# MP257_18x18.net
KiCad netlist of a schematic drawn in Altium Designer
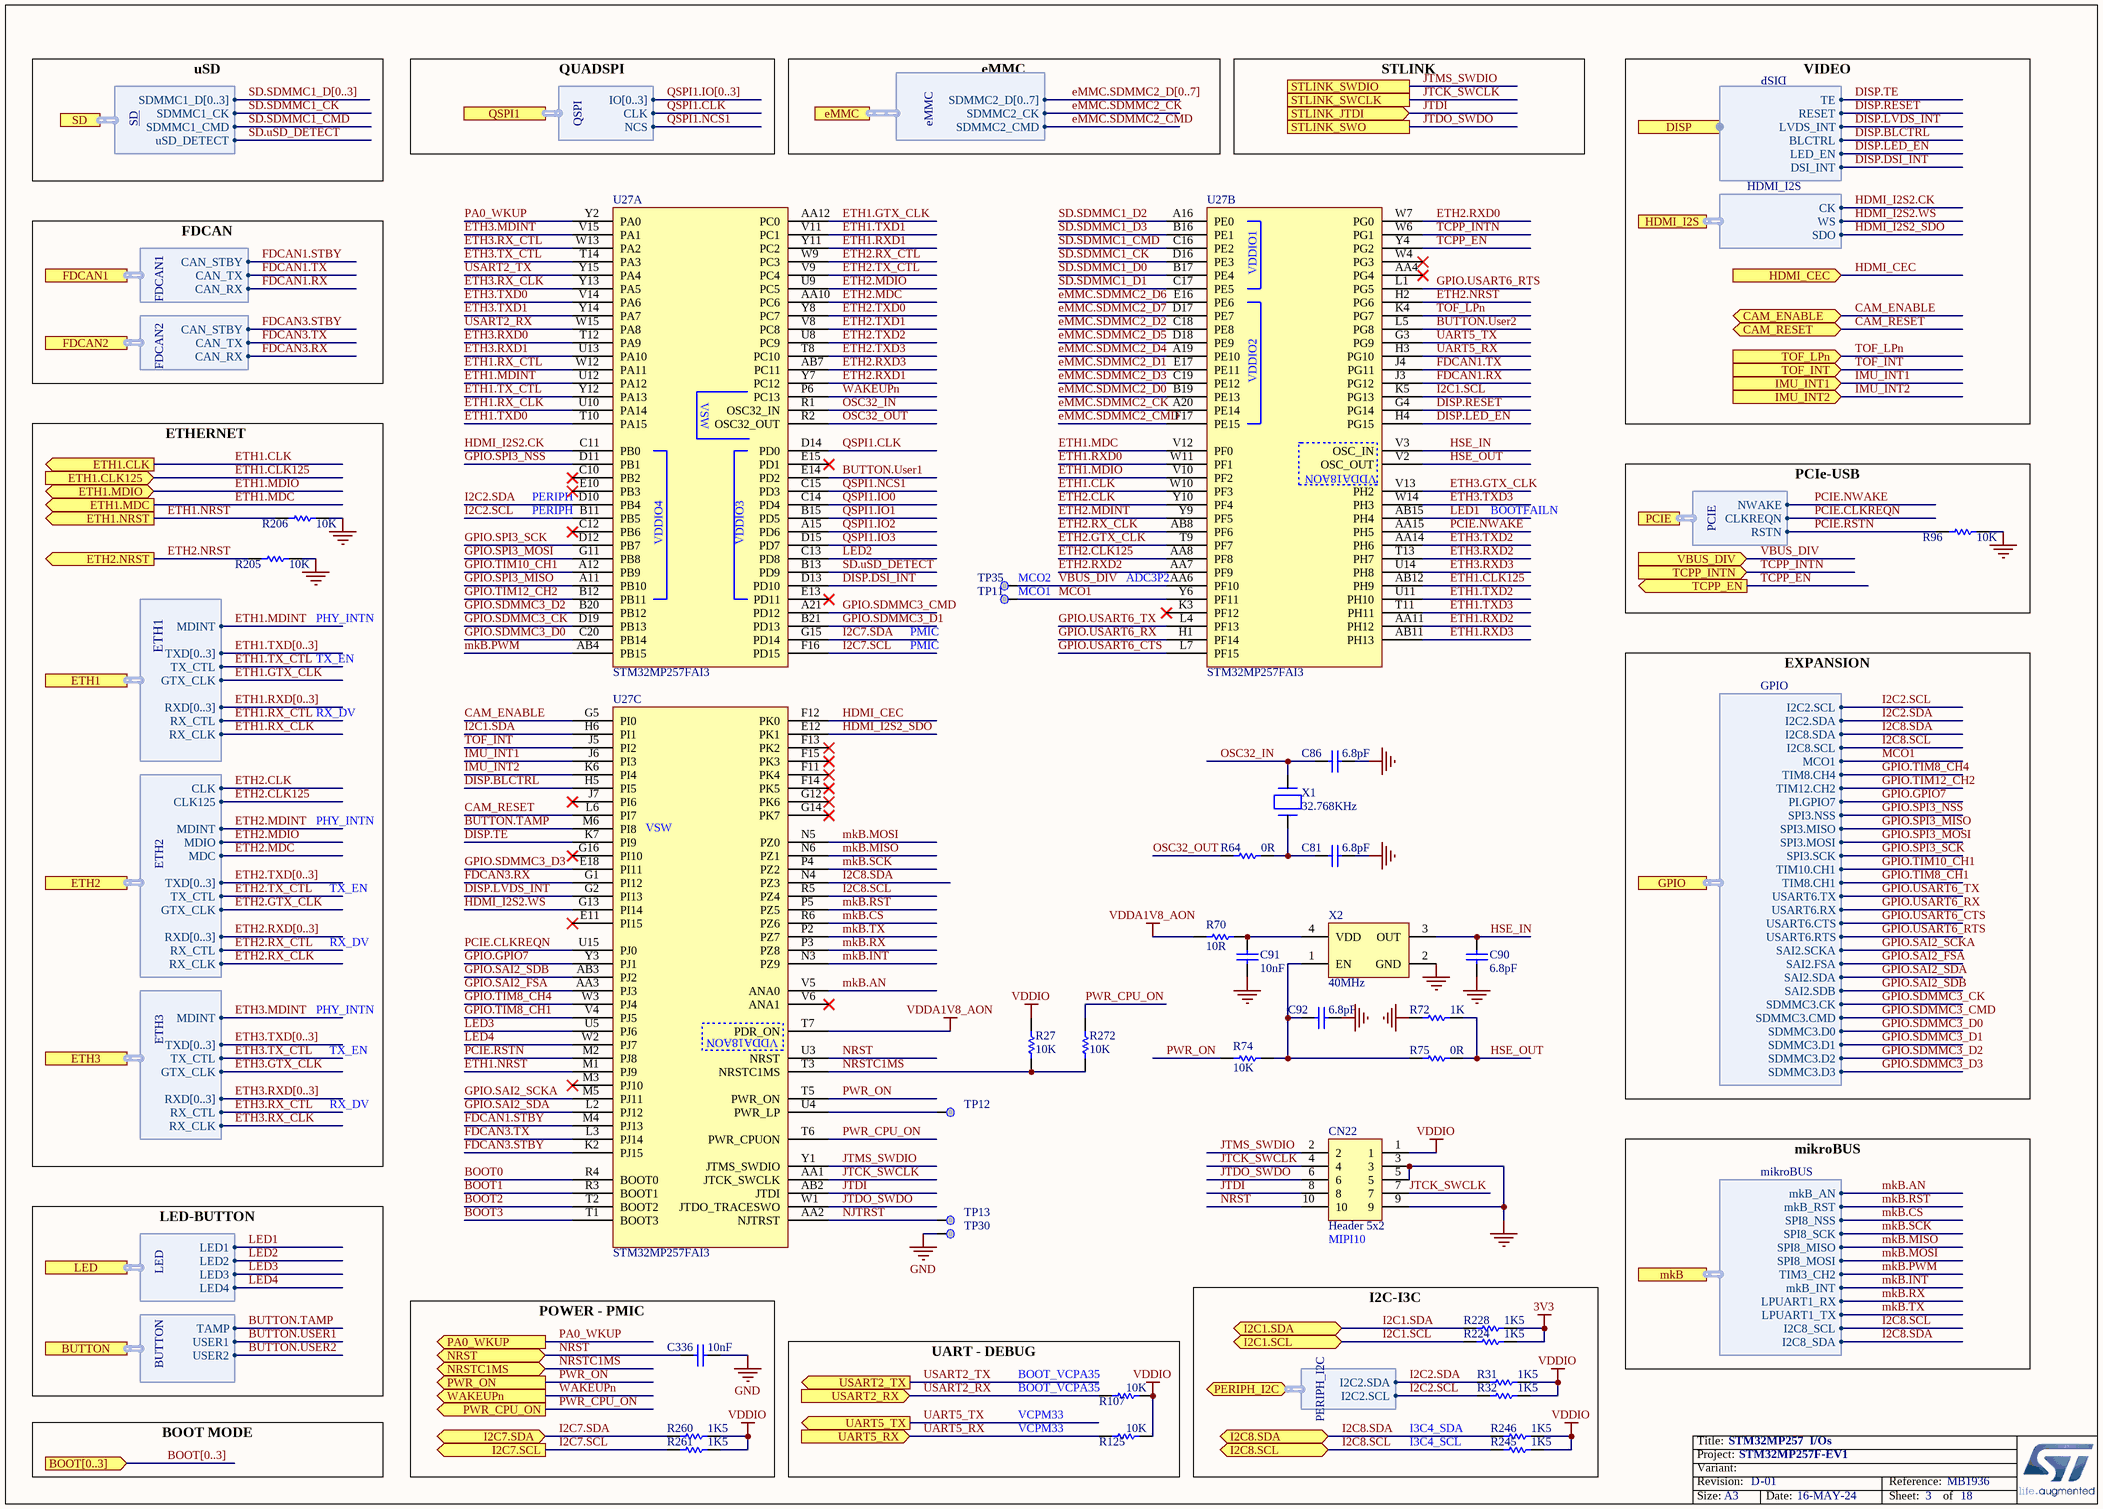
[diagram p0: MP257_18x18.SchDoc]

(export (version "E")
  (design (tool "Eeschema 10.0.6"))
  (components
    (comp (ref "C81")
      (value "6.8pF")
      (footprint "MCD_PARTS:C0402")
      (description "Capacitor, MLCC, 6.8pF, 50V, NPO, +-0.25pF, 0402, T=0.5mm")
      (fields
        (field (name "INTERNAL_PART_NUMBER") "MCD-00674")
        (field (name "MANUFACTURER_PART_NUMBER") "CC0402CRNPO9BN6R8")
        (field (name "PROVIDED_BY") "SUBCO")
      )
      (libsource (lib "MCD_PARTS_database") (part "Capacitor"))
    )
    (comp (ref "C86")
      (value "6.8pF")
      (footprint "MCD_PARTS:C0402")
      (description "Capacitor, MLCC, 6.8pF, 50V, NPO, +-0.25pF, 0402, T=0.5mm")
      (fields
        (field (name "INTERNAL_PART_NUMBER") "MCD-00674")
        (field (name "MANUFACTURER_PART_NUMBER") "CC0402CRNPO9BN6R8")
        (field (name "PROVIDED_BY") "SUBCO")
      )
      (libsource (lib "MCD_PARTS_database") (part "Capacitor"))
    )
    (comp (ref "C90")
      (value "6.8pF")
      (footprint "MCD_PARTS:C0402")
      (description "Capacitor, MLCC, 6.8pF, 50V, NPO, +-0.25pF, 0402, T=0.5mm")
      (fields
        (field (name "INTERNAL_PART_NUMBER") "MCD-00674")
        (field (name "MANUFACTURER_PART_NUMBER") "CC0402CRNPO9BN6R8")
        (field (name "PROVIDED_BY") "SUBCO")
      )
      (libsource (lib "MCD_PARTS_database") (part "Capacitor"))
    )
    (comp (ref "C91")
      (value "10nF")
      (footprint "MCD_PARTS:C0402")
      (description "Capacitor, MLCC, 10nF, 16V, X7R, 10%, 0402, T=0.5mm")
      (fields
        (field (name "INTERNAL_PART_NUMBER") "MCD-00011")
        (field (name "MANUFACTURER_PART_NUMBER") "CC0402KRX7R7BB103")
        (field (name "PROVIDED_BY") "SUBCO")
      )
      (libsource (lib "MCD_PARTS_database") (part "Capacitor"))
    )
    (comp (ref "C92")
      (value "6.8pF")
      (footprint "MCD_PARTS:C0402")
      (description "Capacitor, MLCC, 6.8pF, 50V, NPO, +-0.25pF, 0402, T=0.5mm")
      (fields
        (field (name "INTERNAL_PART_NUMBER") "MCD-00674")
        (field (name "MANUFACTURER_PART_NUMBER") "CC0402CRNPO9BN6R8")
        (field (name "PROVIDED_BY") "SUBCO")
      )
      (libsource (lib "MCD_PARTS_database") (part "Capacitor"))
    )
    (comp (ref "C336")
      (value "10nF")
      (footprint "MCD_PARTS:C0402")
      (description "Capacitor, MLCC, 10nF, 16V, X7R, 10%, 0402, T=0.5mm")
      (fields
        (field (name "INTERNAL_PART_NUMBER") "MCD-00011")
        (field (name "MANUFACTURER_PART_NUMBER") "CC0402KRX7R7BB103")
        (field (name "PROVIDED_BY") "SUBCO")
      )
      (libsource (lib "MCD_PARTS_database") (part "Capacitor"))
    )
    (comp (ref "CN22")
      (value "Header 5x2")
      (footprint "MCD_PARTS:CON_SAMTEC_FTSH-105-01-L-DV-K")
      (description "Header, 5x2, 1.27mm, VR, SMD, T=5.97mm")
      (fields (field (name "INTERNAL_PART_NUMBER") "MCD-01951") (field (name "MANUFACTURER") "SAMTEC"))
      (libsource (lib "MCD_PARTS_database") (part "Header 5x2"))
    )
    (comp (ref "R27")
      (value "10K")
      (footprint "MCD_PARTS:R0402")
      (description "Resistor,10K,0402,1%,1/16W")
      (fields (field (name "INTERNAL_PART_NUMBER") "MCD-00053") (field (name "BMS_PART_NUMBER") "9131590"))
      (libsource (lib "MCD_PARTS_database") (part "Resistor"))
    )
    (comp (ref "R31")
      (value "1K5")
      (footprint "MCD_PARTS:R0402")
      (description "Resistor,1K5,0402,1%,1/16W")
      (fields (field (name "INTERNAL_PART_NUMBER") "MCD-00068") (field (name "MANUFACTURER") "YAGEO"))
      (libsource (lib "MCD_PARTS_database") (part "Resistor"))
    )
    (comp (ref "R32")
      (value "1K5")
      (footprint "MCD_PARTS:R0402")
      (description "Resistor,1K5,0402,1%,1/16W")
      (fields (field (name "INTERNAL_PART_NUMBER") "MCD-00068") (field (name "MANUFACTURER") "YAGEO"))
      (libsource (lib "MCD_PARTS_database") (part "Resistor"))
    )
    (comp (ref "R64")
      (value "0R")
      (footprint "MCD_PARTS:R0402")
      (description "Resistor,0R,0402,5%,1/16W")
      (fields
        (field (name "INTERNAL_PART_NUMBER") "MCD-00052")
        (field (name "MANUFACTURER_PART_NUMBER") "RC0402JR-070RL")
        (field (name "PROVIDED_BY") "SUBCO")
      )
      (libsource (lib "MCD_PARTS_database") (part "Resistor"))
    )
    (comp (ref "R70")
      (value "10R")
      (footprint "MCD_PARTS:R0402")
      (description "Resistor,10R,0402,1%,1/16W")
      (fields
        (field (name "INTERNAL_PART_NUMBER") "MCD-00358")
        (field (name "MANUFACTURER_PART_NUMBER") "RC0402FR-0710RL")
        (field (name "PROVIDED_BY") "SUBCO")
      )
      (libsource (lib "MCD_PARTS_database") (part "Resistor"))
    )
    (comp (ref "R72")
      (value "1K")
      (footprint "MCD_PARTS:R0402")
      (description "Resistor,1K,0402,1%,1/16W")
      (fields
        (field (name "INTERNAL_PART_NUMBER") "MCD-00061")
        (field (name "MANUFACTURER_PART_NUMBER") "RC0402FR-071KL")
        (field (name "PROVIDED_BY") "SUBCO")
      )
      (libsource (lib "MCD_PARTS_database") (part "Resistor"))
    )
    (comp (ref "R74")
      (value "10K")
      (footprint "MCD_PARTS:R0402")
      (description "Resistor,10K,0402,1%,1/16W")
      (fields (field (name "INTERNAL_PART_NUMBER") "MCD-00053") (field (name "BMS_PART_NUMBER") "9131590"))
      (libsource (lib "MCD_PARTS_database") (part "Resistor"))
    )
    (comp (ref "R75")
      (value "0R")
      (footprint "MCD_PARTS:R0402")
      (description "Resistor,0R,0402,5%,1/16W")
      (fields
        (field (name "INTERNAL_PART_NUMBER") "MCD-00052")
        (field (name "MANUFACTURER_PART_NUMBER") "RC0402JR-070RL")
        (field (name "PROVIDED_BY") "SUBCO")
      )
      (libsource (lib "MCD_PARTS_database") (part "Resistor"))
    )
    (comp (ref "R96")
      (value "10K")
      (footprint "MCD_PARTS:R0402")
      (description "Resistor,10K,0402,1%,1/16W")
      (fields
        (field (name "INTERNAL_PART_NUMBER") "MCD-00053")
        (field (name "MANUFACTURER_PART_NUMBER") "RC0402FR-0710KL")
      )
      (libsource (lib "MCD_PARTS_database") (part "Resistor"))
    )
    (comp (ref "R107")
      (value "10K")
      (footprint "MCD_PARTS:R0402")
      (description "Resistor,10K,0402,1%,1/16W")
      (fields (field (name "INTERNAL_PART_NUMBER") "MCD-00053") (field (name "BMS_PART_NUMBER") "9131590"))
      (libsource (lib "MCD_PARTS_database") (part "Resistor"))
    )
    (comp (ref "R125")
      (value "10K")
      (footprint "MCD_PARTS:R0402")
      (description "Resistor,10K,0402,1%,1/16W")
      (fields (field (name "INTERNAL_PART_NUMBER") "MCD-00053") (field (name "BMS_PART_NUMBER") "9131590"))
      (libsource (lib "MCD_PARTS_database") (part "Resistor"))
    )
    (comp (ref "R205")
      (value "10K")
      (footprint "MCD_PARTS:R0402")
      (description "Resistor,10K,0402,1%,1/16W")
      (fields
        (field (name "INTERNAL_PART_NUMBER") "MCD-00053")
        (field (name "MANUFACTURER_PART_NUMBER") "RC0402FR-0710KL")
      )
      (libsource (lib "MCD_PARTS_database") (part "Resistor"))
    )
    (comp (ref "R206")
      (value "10K")
      (footprint "MCD_PARTS:R0402")
      (description "Resistor,10K,0402,1%,1/16W")
      (fields
        (field (name "INTERNAL_PART_NUMBER") "MCD-00053")
        (field (name "MANUFACTURER_PART_NUMBER") "RC0402FR-0710KL")
      )
      (libsource (lib "MCD_PARTS_database") (part "Resistor"))
    )
    (comp (ref "R224")
      (value "1K5")
      (footprint "MCD_PARTS:R0402")
      (description "Resistor,1K5,0402,1%,1/16W")
      (fields (field (name "INTERNAL_PART_NUMBER") "MCD-00068") (field (name "MANUFACTURER") "YAGEO"))
      (libsource (lib "MCD_PARTS_database") (part "Resistor"))
    )
    (comp (ref "R228")
      (value "1K5")
      (footprint "MCD_PARTS:R0402")
      (description "Resistor,1K5,0402,1%,1/16W")
      (fields (field (name "INTERNAL_PART_NUMBER") "MCD-00068") (field (name "MANUFACTURER") "YAGEO"))
      (libsource (lib "MCD_PARTS_database") (part "Resistor"))
    )
    (comp (ref "R245")
      (value "1K5")
      (footprint "MCD_PARTS:R0402")
      (description "Resistor,1K5,0402,1%,1/16W")
      (fields (field (name "INTERNAL_PART_NUMBER") "MCD-00068") (field (name "MANUFACTURER") "YAGEO"))
      (libsource (lib "MCD_PARTS_database") (part "Resistor"))
    )
    (comp (ref "R246")
      (value "1K5")
      (footprint "MCD_PARTS:R0402")
      (description "Resistor,1K5,0402,1%,1/16W")
      (fields (field (name "INTERNAL_PART_NUMBER") "MCD-00068") (field (name "MANUFACTURER") "YAGEO"))
      (libsource (lib "MCD_PARTS_database") (part "Resistor"))
    )
    (comp (ref "R260")
      (value "1K5")
      (footprint "MCD_PARTS:R0402")
      (description "Resistor,1K5,0402,1%,1/16W")
      (fields (field (name "INTERNAL_PART_NUMBER") "MCD-00068") (field (name "MANUFACTURER") "YAGEO"))
      (libsource (lib "MCD_PARTS_database") (part "Resistor"))
    )
    (comp (ref "R261")
      (value "1K5")
      (footprint "MCD_PARTS:R0402")
      (description "Resistor,1K5,0402,1%,1/16W")
      (fields (field (name "INTERNAL_PART_NUMBER") "MCD-00068") (field (name "MANUFACTURER") "YAGEO"))
      (libsource (lib "MCD_PARTS_database") (part "Resistor"))
    )
    (comp (ref "R272")
      (value "10K")
      (footprint "MCD_PARTS:R0402")
      (description "Resistor,10K,0402,1%,1/16W")
      (fields (field (name "INTERNAL_PART_NUMBER") "MCD-00053") (field (name "BMS_PART_NUMBER") "9131590"))
      (libsource (lib "MCD_PARTS_database") (part "Resistor"))
    )
    (comp (ref "TP11")
      (value "Test Point")
      (footprint "MCD_PARTS:TP_SMD_1MM")
      (description "Test Point 1mm")
      (fields
        (field (name "INTERNAL_PART_NUMBER") "MCD-00074")
        (field (name "MANUFACTURER_PART_NUMBER") "n/a")
      )
      (libsource (lib "") (part "Test Point_1"))
    )
    (comp (ref "TP12")
      (value "Test Point")
      (footprint "MCD_PARTS:TP_SMD_1MM")
      (description "Test Point 1mm")
      (fields
        (field (name "INTERNAL_PART_NUMBER") "MCD-00074")
        (field (name "MANUFACTURER_PART_NUMBER") "n/a")
      )
      (libsource (lib "MCD_PARTS_database") (part "Test Point"))
    )
    (comp (ref "TP13")
      (value "Test Point")
      (footprint "MCD_PARTS:TP_SMD_1MM")
      (description "Test Point 1mm")
      (fields
        (field (name "INTERNAL_PART_NUMBER") "MCD-00074")
        (field (name "MANUFACTURER_PART_NUMBER") "n/a")
      )
      (libsource (lib "MCD_PARTS_database") (part "Test Point"))
    )
    (comp (ref "TP30")
      (value "Test Point")
      (footprint "MCD_PARTS:TP_SMD_1MM")
      (description "Test Point 1mm")
      (fields
        (field (name "INTERNAL_PART_NUMBER") "MCD-00074")
        (field (name "MANUFACTURER_PART_NUMBER") "n/a")
      )
      (libsource (lib "MCD_PARTS_database") (part "Test Point"))
    )
    (comp (ref "TP35")
      (value "Test Point")
      (footprint "MCD_PARTS:TP_SMD_1MM")
      (description "Test Point 1mm")
      (fields
        (field (name "INTERNAL_PART_NUMBER") "MCD-00074")
        (field (name "MANUFACTURER_PART_NUMBER") "n/a")
      )
      (libsource (lib "") (part "Test Point_1"))
    )
    (comp (ref "U27")
      (value "STM32MP257FAI3")
      (footprint "ICC_LFBGA436_18X18_P080_H1P70_STM32MP257_CODE-B0D1")
      (description "MPU, ARM Cortex-A35 + M33 32-bit MPU, 808KB RAM, With Crypto")
      (fields
        (field (name "INTERNAL_PART_NUMBER") "MCD-02000")
        (field (name "MANUFACTURER") "STMICROELECTRONICS")
      )
      (libsource (lib "MCD_PARTS_database") (part "STM32MP257FAI3"))
    )
    (comp (ref "X1")
      (value "32.768KHz")
      (footprint "MCD_PARTS:CRY_NX2012SA_2P")
      (description "Crystal, 32.768kHz, 6pF, +/-20ppm, 80K, 2.05x1.2mm")
      (fields (field (name "INTERNAL_PART_NUMBER") "MCD-01479") (field (name "BMS_PART_NUMBER") "9157049"))
      (libsource (lib "MCD_PARTS_database") (part "XTAL_2_PINS"))
    )
    (comp (ref "X2")
      (value "40MHz")
      (footprint "MCD_PARTS:CRY_NZ1612SH_4P")
      (description "Oscillator, SPXO, 40Mhz, +/-50ppm, 1.8V, square wave, 1.6x1.2mm")
      (fields (field (name "INTERNAL_PART_NUMBER") "MCD-02343") (field (name "MANUFACTURER") "NDK"))
      (libsource (lib "MCD_PARTS_database") (part "OSCILLATOR_4_PINS"))
    )
  )
  (nets
    (net (code "18") (name "/BOOT0") (class "Default")
      (node (ref "U27") (pin "R4") (pinfunction "BOOT0_R4") (pintype "passive"))
    )
    (net (code "19") (name "/BOOT1") (class "Default")
      (node (ref "U27") (pin "R3") (pinfunction "BOOT1_R3") (pintype "passive"))
    )
    (net (code "20") (name "/BOOT2") (class "Default")
      (node (ref "U27") (pin "T2") (pinfunction "BOOT2_T2") (pintype "passive"))
    )
    (net (code "21") (name "/BOOT3") (class "Default")
      (node (ref "U27") (pin "T1") (pinfunction "BOOT3_T1") (pintype "passive"))
    )
    (net (code "23") (name "/BUTTON.TAMP") (class "Default")
      (node (ref "U27") (pin "M6") (pinfunction "PI8_M6") (pintype "passive"))
    )
    (net (code "26") (name "/BUTTON.User1") (class "Default")
      (node (ref "U27") (pin "E14") (pinfunction "PD2_E14") (pintype "passive"))
    )
    (net (code "27") (name "/BUTTON.User2") (class "Default")
      (node (ref "U27") (pin "L5") (pinfunction "PG8_L5") (pintype "passive"))
    )
    (net (code "28") (name "/CAM_ENABLE") (class "Default")
      (node (ref "U27") (pin "G5") (pinfunction "PI0_G5") (pintype "passive"))
    )
    (net (code "29") (name "/CAM_RESET") (class "Default")
      (node (ref "U27") (pin "L6") (pinfunction "PI7_L6") (pintype "passive"))
    )
    (net (code "30") (name "/DISP.BLCTRL") (class "Default")
      (node (ref "U27") (pin "H5") (pinfunction "PI5_H5") (pintype "passive"))
    )
    (net (code "31") (name "/DISP.DSI_INT") (class "Default")
      (node (ref "U27") (pin "D13") (pinfunction "PD10_D13") (pintype "passive"))
    )
    (net (code "32") (name "/DISP.LED_EN") (class "Default")
      (node (ref "U27") (pin "H4") (pinfunction "PG15_H4") (pintype "passive"))
    )
    (net (code "33") (name "/DISP.LVDS_INT") (class "Default")
      (node (ref "U27") (pin "G2") (pinfunction "PI13_G2") (pintype "passive"))
    )
    (net (code "34") (name "/DISP.RESET") (class "Default")
      (node (ref "U27") (pin "G4") (pinfunction "PG14_G4") (pintype "passive"))
    )
    (net (code "35") (name "/DISP.TE") (class "Default")
      (node (ref "U27") (pin "K7") (pinfunction "PI9_K7") (pintype "passive"))
    )
    (net (code "36") (name "/ETH1.CLK") (class "Default")
      (node (ref "U27") (pin "W10") (pinfunction "PF3_W10") (pintype "passive"))
    )
    (net (code "37") (name "/ETH1.CLK125") (class "Default")
      (node (ref "U27") (pin "AB12") (pinfunction "PH9_AB12") (pintype "passive"))
    )
    (net (code "38") (name "/ETH1.GTX_CLK") (class "Default")
      (node (ref "U27") (pin "AA12") (pinfunction "PC0_AA12") (pintype "passive"))
    )
    (net (code "39") (name "/ETH1.MDC") (class "Default")
      (node (ref "U27") (pin "V12") (pinfunction "PF0_V12") (pintype "passive"))
    )
    (net (code "40") (name "/ETH1.MDINT") (class "Default")
      (node (ref "U27") (pin "U12") (pinfunction "PA12_U12") (pintype "passive"))
    )
    (net (code "41") (name "/ETH1.MDIO") (class "Default")
      (node (ref "U27") (pin "V10") (pinfunction "PF2_V10") (pintype "passive"))
    )
    (net (code "42") (name "/ETH1.NRST") (class "Default")
      (node (ref "R206") (pin "1") (pinfunction "1_1") (pintype "passive"))
      (node (ref "U27") (pin "M1") (pinfunction "PJ9_M1") (pintype "passive"))
    )
    (net (code "43") (name "/ETH1.RXD0") (class "Default")
      (node (ref "U27") (pin "W11") (pinfunction "PF1_W11") (pintype "passive"))
    )
    (net (code "44") (name "/ETH1.RXD1") (class "Default")
      (node (ref "U27") (pin "Y11") (pinfunction "PC2_Y11") (pintype "passive"))
    )
    (net (code "45") (name "/ETH1.RXD2") (class "Default")
      (node (ref "U27") (pin "AA11") (pinfunction "PH12_AA11") (pintype "passive"))
    )
    (net (code "46") (name "/ETH1.RXD3") (class "Default")
      (node (ref "U27") (pin "AB11") (pinfunction "PH13_AB11") (pintype "passive"))
    )
    (net (code "48") (name "/ETH1.RX_CLK") (class "Default")
      (node (ref "U27") (pin "U10") (pinfunction "PA14_U10") (pintype "passive"))
    )
    (net (code "49") (name "/ETH1.RX_CTL") (class "Default")
      (node (ref "U27") (pin "W12") (pinfunction "PA11_W12") (pintype "passive"))
    )
    (net (code "50") (name "/ETH1.TXD0") (class "Default")
      (node (ref "U27") (pin "T10") (pinfunction "PA15_T10") (pintype "passive"))
    )
    (net (code "51") (name "/ETH1.TXD1") (class "Default")
      (node (ref "U27") (pin "V11") (pinfunction "PC1_V11") (pintype "passive"))
    )
    (net (code "52") (name "/ETH1.TXD2") (class "Default")
      (node (ref "U27") (pin "U11") (pinfunction "PH10_U11") (pintype "passive"))
    )
    (net (code "53") (name "/ETH1.TXD3") (class "Default")
      (node (ref "U27") (pin "T11") (pinfunction "PH11_T11") (pintype "passive"))
    )
    (net (code "54") (name "/ETH1.TX_CTL") (class "Default")
      (node (ref "U27") (pin "Y12") (pinfunction "PA13_Y12") (pintype "passive"))
    )
    (net (code "56") (name "/ETH2.CLK") (class "Default")
      (node (ref "U27") (pin "Y10") (pinfunction "PF4_Y10") (pintype "passive"))
    )
    (net (code "57") (name "/ETH2.CLK125") (class "Default")
      (node (ref "U27") (pin "AA8") (pinfunction "PF8_AA8") (pintype "passive"))
    )
    (net (code "58") (name "/ETH2.GTX_CLK") (class "Default")
      (node (ref "U27") (pin "T9") (pinfunction "PF7_T9") (pintype "passive"))
    )
    (net (code "59") (name "/ETH2.MDC") (class "Default")
      (node (ref "U27") (pin "AA10") (pinfunction "PC6_AA10") (pintype "passive"))
    )
    (net (code "60") (name "/ETH2.MDINT") (class "Default")
      (node (ref "U27") (pin "Y9") (pinfunction "PF5_Y9") (pintype "passive"))
    )
    (net (code "61") (name "/ETH2.MDIO") (class "Default")
      (node (ref "U27") (pin "U9") (pinfunction "PC5_U9") (pintype "passive"))
    )
    (net (code "62") (name "/ETH2.NRST") (class "Default")
      (node (ref "R205") (pin "1") (pinfunction "1_1") (pintype "passive"))
      (node (ref "U27") (pin "H2") (pinfunction "PG6_H2") (pintype "passive"))
    )
    (net (code "63") (name "/ETH2.RXD0") (class "Default")
      (node (ref "U27") (pin "W7") (pinfunction "PG0_W7") (pintype "passive"))
    )
    (net (code "64") (name "/ETH2.RXD1") (class "Default")
      (node (ref "U27") (pin "Y7") (pinfunction "PC12_Y7") (pintype "passive"))
    )
    (net (code "65") (name "/ETH2.RXD2") (class "Default")
      (node (ref "U27") (pin "AA7") (pinfunction "PF9_AA7") (pintype "passive"))
    )
    (net (code "66") (name "/ETH2.RXD3") (class "Default")
      (node (ref "U27") (pin "AB7") (pinfunction "PC11_AB7") (pintype "passive"))
    )
    (net (code "67") (name "/ETH2.RX_CLK") (class "Default")
      (node (ref "U27") (pin "AB8") (pinfunction "PF6_AB8") (pintype "passive"))
    )
    (net (code "68") (name "/ETH2.RX_CTL") (class "Default")
      (node (ref "U27") (pin "W9") (pinfunction "PC3_W9") (pintype "passive"))
    )
    (net (code "69") (name "/ETH2.TXD0") (class "Default")
      (node (ref "U27") (pin "Y8") (pinfunction "PC7_Y8") (pintype "passive"))
    )
    (net (code "70") (name "/ETH2.TXD1") (class "Default")
      (node (ref "U27") (pin "V8") (pinfunction "PC8_V8") (pintype "passive"))
    )
    (net (code "71") (name "/ETH2.TXD2") (class "Default")
      (node (ref "U27") (pin "U8") (pinfunction "PC9_U8") (pintype "passive"))
    )
    (net (code "72") (name "/ETH2.TXD3") (class "Default")
      (node (ref "U27") (pin "T8") (pinfunction "PC10_T8") (pintype "passive"))
    )
    (net (code "74") (name "/ETH2.TX_CTL") (class "Default")
      (node (ref "U27") (pin "V9") (pinfunction "PC4_V9") (pintype "passive"))
    )
    (net (code "76") (name "/ETH3.GTX_CLK") (class "Default")
      (node (ref "U27") (pin "V13") (pinfunction "PH2_V13") (pintype "passive"))
    )
    (net (code "77") (name "/ETH3.MDINT") (class "Default")
      (node (ref "U27") (pin "V15") (pinfunction "PA1_V15") (pintype "passive"))
    )
    (net (code "78") (name "/ETH3.RXD0") (class "Default")
      (node (ref "U27") (pin "T12") (pinfunction "PA9_T12") (pintype "passive"))
    )
    (net (code "79") (name "/ETH3.RXD1") (class "Default")
      (node (ref "U27") (pin "U13") (pinfunction "PA10_U13") (pintype "passive"))
    )
    (net (code "80") (name "/ETH3.RXD2") (class "Default")
      (node (ref "U27") (pin "T13") (pinfunction "PH7_T13") (pintype "passive"))
    )
    (net (code "81") (name "/ETH3.RXD3") (class "Default")
      (node (ref "U27") (pin "U14") (pinfunction "PH8_U14") (pintype "passive"))
    )
    (net (code "83") (name "/ETH3.RX_CLK") (class "Default")
      (node (ref "U27") (pin "Y13") (pinfunction "PA5_Y13") (pintype "passive"))
    )
    (net (code "84") (name "/ETH3.RX_CTL") (class "Default")
      (node (ref "U27") (pin "W13") (pinfunction "PA2_W13") (pintype "passive"))
    )
    (net (code "85") (name "/ETH3.TXD0") (class "Default")
      (node (ref "U27") (pin "V14") (pinfunction "PA6_V14") (pintype "passive"))
    )
    (net (code "86") (name "/ETH3.TXD1") (class "Default")
      (node (ref "U27") (pin "Y14") (pinfunction "PA7_Y14") (pintype "passive"))
    )
    (net (code "87") (name "/ETH3.TXD2") (class "Default")
      (node (ref "U27") (pin "AA14") (pinfunction "PH6_AA14") (pintype "passive"))
    )
    (net (code "88") (name "/ETH3.TXD3") (class "Default")
      (node (ref "U27") (pin "W14") (pinfunction "PH3_W14") (pintype "passive"))
    )
    (net (code "89") (name "/ETH3.TX_CTL") (class "Default")
      (node (ref "U27") (pin "T14") (pinfunction "PA3_T14") (pintype "passive"))
    )
    (net (code "91") (name "/FDCAN1.RX") (class "Default")
      (node (ref "U27") (pin "J3") (pinfunction "PG12_J3") (pintype "passive"))
    )
    (net (code "92") (name "/FDCAN1.STBY") (class "Default")
      (node (ref "U27") (pin "M4") (pinfunction "PJ13_M4") (pintype "passive"))
    )
    (net (code "93") (name "/FDCAN1.TX") (class "Default")
      (node (ref "U27") (pin "J4") (pinfunction "PG11_J4") (pintype "passive"))
    )
    (net (code "94") (name "/FDCAN3.RX") (class "Default")
      (node (ref "U27") (pin "G1") (pinfunction "PI12_G1") (pintype "passive"))
    )
    (net (code "95") (name "/FDCAN3.STBY") (class "Default")
      (node (ref "U27") (pin "K2") (pinfunction "PJ15_K2") (pintype "passive"))
    )
    (net (code "96") (name "/FDCAN3.TX") (class "Default")
      (node (ref "U27") (pin "L3") (pinfunction "PJ14_L3") (pintype "passive"))
    )
    (net (code "97") (name "/GPIO.GPIO7") (class "Default")
      (node (ref "U27") (pin "Y3") (pinfunction "PJ1_Y3") (pintype "passive"))
    )
    (net (code "98") (name "/GPIO.SAI2_FSA") (class "Default")
      (node (ref "U27") (pin "AA3") (pinfunction "PJ3_AA3") (pintype "passive"))
    )
    (net (code "99") (name "/GPIO.SAI2_SCKA") (class "Default")
      (node (ref "U27") (pin "M5") (pinfunction "PJ11_M5") (pintype "passive"))
    )
    (net (code "100") (name "/GPIO.SAI2_SDA") (class "Default")
      (node (ref "U27") (pin "L2") (pinfunction "PJ12_L2") (pintype "passive"))
    )
    (net (code "101") (name "/GPIO.SAI2_SDB") (class "Default")
      (node (ref "U27") (pin "AB3") (pinfunction "PJ2_AB3") (pintype "passive"))
    )
    (net (code "102") (name "/GPIO.SDMMC3_CK") (class "Default")
      (node (ref "U27") (pin "D19") (pinfunction "PB13_D19") (pintype "passive"))
    )
    (net (code "103") (name "/GPIO.SDMMC3_CMD") (class "Default")
      (node (ref "U27") (pin "A21") (pinfunction "PD12_A21") (pintype "passive"))
    )
    (net (code "104") (name "/GPIO.SDMMC3_D0") (class "Default")
      (node (ref "U27") (pin "C20") (pinfunction "PB14_C20") (pintype "passive"))
    )
    (net (code "105") (name "/GPIO.SDMMC3_D1") (class "Default")
      (node (ref "U27") (pin "B21") (pinfunction "PD13_B21") (pintype "passive"))
    )
    (net (code "106") (name "/GPIO.SDMMC3_D2") (class "Default")
      (node (ref "U27") (pin "B20") (pinfunction "PB12_B20") (pintype "passive"))
    )
    (net (code "107") (name "/GPIO.SDMMC3_D3") (class "Default")
      (node (ref "U27") (pin "E18") (pinfunction "PI11_E18") (pintype "passive"))
    )
    (net (code "108") (name "/GPIO.SPI3_MISO") (class "Default")
      (node (ref "U27") (pin "A11") (pinfunction "PB10_A11") (pintype "passive"))
    )
    (net (code "109") (name "/GPIO.SPI3_MOSI") (class "Default")
      (node (ref "U27") (pin "G11") (pinfunction "PB8_G11") (pintype "passive"))
    )
    (net (code "110") (name "/GPIO.SPI3_NSS") (class "Default")
      (node (ref "U27") (pin "D11") (pinfunction "PB1_D11") (pintype "passive"))
    )
    (net (code "111") (name "/GPIO.SPI3_SCK") (class "Default")
      (node (ref "U27") (pin "D12") (pinfunction "PB7_D12") (pintype "passive"))
    )
    (net (code "112") (name "/GPIO.TIM8_CH1") (class "Default")
      (node (ref "U27") (pin "V4") (pinfunction "PJ5_V4") (pintype "passive"))
    )
    (net (code "113") (name "/GPIO.TIM8_CH4") (class "Default")
      (node (ref "U27") (pin "W3") (pinfunction "PJ4_W3") (pintype "passive"))
    )
    (net (code "114") (name "/GPIO.TIM10_CH1") (class "Default")
      (node (ref "U27") (pin "A12") (pinfunction "PB9_A12") (pintype "passive"))
    )
    (net (code "115") (name "/GPIO.TIM12_CH2") (class "Default")
      (node (ref "U27") (pin "B12") (pinfunction "PB11_B12") (pintype "passive"))
    )
    (net (code "116") (name "/GPIO.USART6_CTS") (class "Default")
      (node (ref "U27") (pin "L7") (pinfunction "PF15_L7") (pintype "passive"))
    )
    (net (code "117") (name "/GPIO.USART6_RTS") (class "Default")
      (node (ref "U27") (pin "L1") (pinfunction "PG5_L1") (pintype "passive"))
    )
    (net (code "118") (name "/GPIO.USART6_RX") (class "Default")
      (node (ref "U27") (pin "H1") (pinfunction "PF14_H1") (pintype "passive"))
    )
    (net (code "119") (name "/GPIO.USART6_TX") (class "Default")
      (node (ref "U27") (pin "L4") (pinfunction "PF13_L4") (pintype "passive"))
    )
    (net (code "120") (name "/HDMI_CEC") (class "Default")
      (node (ref "U27") (pin "F12") (pinfunction "PK0_F12") (pintype "passive"))
    )
    (net (code "121") (name "/HDMI_I2S2.CK") (class "Default")
      (node (ref "U27") (pin "C11") (pinfunction "PB0_C11") (pintype "passive"))
    )
    (net (code "122") (name "/HDMI_I2S2.WS") (class "Default")
      (node (ref "U27") (pin "G13") (pinfunction "PI14_G13") (pintype "passive"))
    )
    (net (code "123") (name "/HDMI_I2S2_SDO") (class "Default")
      (node (ref "U27") (pin "E12") (pinfunction "PK1_E12") (pintype "passive"))
    )
    (net (code "124") (name "/HSE_IN") (class "Default")
      (node (ref "C90") (pin "2") (pinfunction "2_2") (pintype "passive"))
      (node (ref "U27") (pin "V3") (pinfunction "OSC_IN_V3") (pintype "passive"))
      (node (ref "X2") (pin "3") (pinfunction "OUT_3") (pintype "passive"))
    )
    (net (code "125") (name "/HSE_OUT") (class "Default")
      (node (ref "R72") (pin "1") (pinfunction "1_1") (pintype "passive"))
      (node (ref "R75") (pin "2") (pinfunction "2_2") (pintype "passive"))
      (node (ref "U27") (pin "V2") (pinfunction "OSC_OUT_V2") (pintype "passive"))
    )
    (net (code "126") (name "/I2C1.SCL") (class "Default")
      (node (ref "R224") (pin "1") (pinfunction "1_1") (pintype "passive"))
      (node (ref "U27") (pin "K5") (pinfunction "PG13_K5") (pintype "passive"))
    )
    (net (code "127") (name "/I2C1.SDA") (class "Default")
      (node (ref "R228") (pin "1") (pinfunction "1_1") (pintype "passive"))
      (node (ref "U27") (pin "H6") (pinfunction "PI1_H6") (pintype "passive"))
    )
    (net (code "128") (name "/I2C2.SCL") (class "Default")
      (node (ref "R32") (pin "1") (pinfunction "1_1") (pintype "passive"))
      (node (ref "U27") (pin "B11") (pinfunction "PB5_B11") (pintype "passive"))
    )
    (net (code "129") (name "/I2C2.SDA") (class "Default")
      (node (ref "R31") (pin "1") (pinfunction "1_1") (pintype "passive"))
      (node (ref "U27") (pin "D10") (pinfunction "PB4_D10") (pintype "passive"))
    )
    (net (code "130") (name "/I2C7.SCL") (class "Default")
      (node (ref "R261") (pin "1") (pinfunction "1_1") (pintype "passive"))
      (node (ref "U27") (pin "F16") (pinfunction "PD15_F16") (pintype "passive"))
    )
    (net (code "131") (name "/I2C7.SDA") (class "Default")
      (node (ref "R260") (pin "1") (pinfunction "1_1") (pintype "passive"))
      (node (ref "U27") (pin "G15") (pinfunction "PD14_G15") (pintype "passive"))
    )
    (net (code "132") (name "/I2C8.SCL") (class "Default")
      (node (ref "R245") (pin "1") (pinfunction "1_1") (pintype "passive"))
      (node (ref "U27") (pin "R5") (pinfunction "PZ4_R5") (pintype "passive"))
    )
    (net (code "133") (name "/I2C8.SDA") (class "Default")
      (node (ref "R246") (pin "1") (pinfunction "1_1") (pintype "passive"))
      (node (ref "U27") (pin "N4") (pinfunction "PZ3_N4") (pintype "passive"))
    )
    (net (code "134") (name "/IMU_INT1") (class "Default")
      (node (ref "U27") (pin "J6") (pinfunction "PI3_J6") (pintype "passive"))
    )
    (net (code "135") (name "/IMU_INT2") (class "Default")
      (node (ref "U27") (pin "K6") (pinfunction "PI4_K6") (pintype "passive"))
    )
    (net (code "136") (name "/JTCK_SWCLK") (class "Default")
      (node (ref "CN22") (pin "4") (pinfunction "4_4") (pintype "passive"))
      (node (ref "CN22") (pin "7") (pinfunction "7_7") (pintype "passive"))
      (node (ref "U27") (pin "AA1") (pinfunction "JTCK_SWCLK_AA1") (pintype "passive"))
    )
    (net (code "137") (name "/JTDI") (class "Default")
      (node (ref "CN22") (pin "8") (pinfunction "8_8") (pintype "passive"))
      (node (ref "U27") (pin "AB2") (pinfunction "JTDI_AB2") (pintype "passive"))
    )
    (net (code "138") (name "/JTDO_SWDO") (class "Default")
      (node (ref "CN22") (pin "6") (pinfunction "6_6") (pintype "passive"))
      (node (ref "U27") (pin "W1") (pinfunction "JTDO_TRACESWO_W1") (pintype "passive"))
    )
    (net (code "139") (name "/JTMS_SWDIO") (class "Default")
      (node (ref "CN22") (pin "2") (pinfunction "2_2") (pintype "passive"))
      (node (ref "U27") (pin "Y1") (pinfunction "JTMS_SWDIO_Y1") (pintype "passive"))
    )
    (net (code "140") (name "/LED1") (class "Default")
      (node (ref "U27") (pin "AB15") (pinfunction "PH4_AB15") (pintype "passive"))
    )
    (net (code "141") (name "/LED2") (class "Default")
      (node (ref "U27") (pin "C13") (pinfunction "PD8_C13") (pintype "passive"))
    )
    (net (code "142") (name "/LED3") (class "Default")
      (node (ref "U27") (pin "U5") (pinfunction "PJ6_U5") (pintype "passive"))
    )
    (net (code "143") (name "/LED4") (class "Default")
      (node (ref "U27") (pin "W2") (pinfunction "PJ7_W2") (pintype "passive"))
    )
    (net (code "144") (name "/MCO1") (class "Default")
      (node (ref "TP11") (pin "1") (pinfunction "1_1") (pintype "passive"))
      (node (ref "U27") (pin "Y6") (pinfunction "PF11_Y6") (pintype "passive"))
    )
    (net (code "145") (name "/NJTRST") (class "Default")
      (node (ref "TP13") (pin "1") (pinfunction "1_1") (pintype "passive"))
      (node (ref "U27") (pin "AA2") (pinfunction "NJTRST_AA2") (pintype "passive"))
    )
    (net (code "146") (name "/NRST") (class "Default")
      (node (ref "C336") (pin "2") (pinfunction "2_2") (pintype "passive"))
      (node (ref "CN22") (pin "10") (pinfunction "10_10") (pintype "passive"))
      (node (ref "U27") (pin "U3") (pinfunction "NRST_U3") (pintype "passive"))
    )
    (net (code "147") (name "/NRSTC1MS") (class "Default")
      (node (ref "R27") (pin "1") (pinfunction "1_1") (pintype "passive"))
      (node (ref "R272") (pin "1") (pinfunction "1_1") (pintype "passive"))
      (node (ref "U27") (pin "T3") (pinfunction "NRSTC1MS_T3") (pintype "passive"))
    )
    (net (code "148") (name "/OSC32_IN") (class "Default")
      (node (ref "C86") (pin "1") (pinfunction "1_1") (pintype "passive"))
      (node (ref "U27") (pin "R1") (pinfunction "OSC32_IN_R1") (pintype "passive"))
      (node (ref "X1") (pin "2") (pinfunction "X2_2") (pintype "passive"))
    )
    (net (code "149") (name "/OSC32_OUT") (class "Default")
      (node (ref "R64") (pin "1") (pinfunction "1_1") (pintype "passive"))
      (node (ref "U27") (pin "R2") (pinfunction "OSC32_OUT_R2") (pintype "passive"))
    )
    (net (code "150") (name "/PA0_WKUP") (class "Default")
      (node (ref "U27") (pin "Y2") (pinfunction "PA0_Y2") (pintype "passive"))
    )
    (net (code "151") (name "/PCIE.CLKREQN") (class "Default")
      (node (ref "U27") (pin "U15") (pinfunction "PJ0_U15") (pintype "passive"))
    )
    (net (code "152") (name "/PCIE.NWAKE") (class "Default")
      (node (ref "U27") (pin "AA15") (pinfunction "PH5_AA15") (pintype "passive"))
    )
    (net (code "153") (name "/PCIE.RSTN") (class "Default")
      (node (ref "R96") (pin "1") (pinfunction "1_1") (pintype "passive"))
      (node (ref "U27") (pin "M2") (pinfunction "PJ8_M2") (pintype "passive"))
    )
    (net (code "154") (name "/PWR_CPU_ON") (class "Default")
      (node (ref "R272") (pin "2") (pinfunction "2_2") (pintype "passive"))
      (node (ref "U27") (pin "T6") (pinfunction "PWR_CPUON_T6") (pintype "passive"))
    )
    (net (code "155") (name "/PWR_ON") (class "Default")
      (node (ref "R74") (pin "2") (pinfunction "2_2") (pintype "passive"))
      (node (ref "U27") (pin "T5") (pinfunction "PWR_ON_T5") (pintype "passive"))
    )
    (net (code "156") (name "/QSPI1.CLK") (class "Default")
      (node (ref "U27") (pin "D14") (pinfunction "PD0_D14") (pintype "passive"))
    )
    (net (code "157") (name "/QSPI1.IO0") (class "Default")
      (node (ref "U27") (pin "C14") (pinfunction "PD4_C14") (pintype "passive"))
    )
    (net (code "158") (name "/QSPI1.IO1") (class "Default")
      (node (ref "U27") (pin "B15") (pinfunction "PD5_B15") (pintype "passive"))
    )
    (net (code "159") (name "/QSPI1.IO2") (class "Default")
      (node (ref "U27") (pin "A15") (pinfunction "PD6_A15") (pintype "passive"))
    )
    (net (code "160") (name "/QSPI1.IO3") (class "Default")
      (node (ref "U27") (pin "D15") (pinfunction "PD7_D15") (pintype "passive"))
    )
    (net (code "162") (name "/QSPI1.NCS1") (class "Default")
      (node (ref "U27") (pin "C15") (pinfunction "PD3_C15") (pintype "passive"))
    )
    (net (code "163") (name "/SD.SDMMC1_CK") (class "Default")
      (node (ref "U27") (pin "D16") (pinfunction "PE3_D16") (pintype "passive"))
    )
    (net (code "164") (name "/SD.SDMMC1_CMD") (class "Default")
      (node (ref "U27") (pin "C16") (pinfunction "PE2_C16") (pintype "passive"))
    )
    (net (code "165") (name "/SD.SDMMC1_D0") (class "Default")
      (node (ref "U27") (pin "B17") (pinfunction "PE4_B17") (pintype "passive"))
    )
    (net (code "166") (name "/SD.SDMMC1_D1") (class "Default")
      (node (ref "U27") (pin "C17") (pinfunction "PE5_C17") (pintype "passive"))
    )
    (net (code "167") (name "/SD.SDMMC1_D2") (class "Default")
      (node (ref "U27") (pin "A16") (pinfunction "PE0_A16") (pintype "passive"))
    )
    (net (code "168") (name "/SD.SDMMC1_D3") (class "Default")
      (node (ref "U27") (pin "B16") (pinfunction "PE1_B16") (pintype "passive"))
    )
    (net (code "169") (name "/SD.uSD_DETECT") (class "Default")
      (node (ref "U27") (pin "B13") (pinfunction "PD9_B13") (pintype "passive"))
    )
    (net (code "171") (name "/TCPP_EN") (class "Default")
      (node (ref "U27") (pin "Y4") (pinfunction "PG2_Y4") (pintype "passive"))
    )
    (net (code "172") (name "/TCPP_INTN") (class "Default")
      (node (ref "U27") (pin "W6") (pinfunction "PG1_W6") (pintype "passive"))
    )
    (net (code "173") (name "/TOF_INT") (class "Default")
      (node (ref "U27") (pin "J5") (pinfunction "PI2_J5") (pintype "passive"))
    )
    (net (code "174") (name "/TOF_LPn") (class "Default")
      (node (ref "U27") (pin "K4") (pinfunction "PG7_K4") (pintype "passive"))
    )
    (net (code "175") (name "/UART5_RX") (class "Default")
      (node (ref "R125") (pin "1") (pinfunction "1_1") (pintype "passive"))
      (node (ref "U27") (pin "H3") (pinfunction "PG10_H3") (pintype "passive"))
    )
    (net (code "176") (name "/UART5_TX") (class "Default")
      (node (ref "U27") (pin "G3") (pinfunction "PG9_G3") (pintype "passive"))
    )
    (net (code "177") (name "/USART2_RX") (class "Default")
      (node (ref "R107") (pin "1") (pinfunction "1_1") (pintype "passive"))
      (node (ref "U27") (pin "W15") (pinfunction "PA8_W15") (pintype "passive"))
    )
    (net (code "178") (name "/USART2_TX") (class "Default")
      (node (ref "U27") (pin "Y15") (pinfunction "PA4_Y15") (pintype "passive"))
    )
    (net (code "179") (name "/VBUS_DIV") (class "Default")
      (node (ref "TP35") (pin "1") (pinfunction "1_1") (pintype "passive"))
      (node (ref "U27") (pin "AA6") (pinfunction "PF10_AA6") (pintype "passive"))
    )
    (net (code "180") (name "/WAKEUPn") (class "Default")
      (node (ref "U27") (pin "P6") (pinfunction "PC13_P6") (pintype "passive"))
    )
    (net (code "181") (name "/eMMC.SDMMC2_CK") (class "Default")
      (node (ref "U27") (pin "A20") (pinfunction "PE14_A20") (pintype "passive"))
    )
    (net (code "182") (name "/eMMC.SDMMC2_CMD") (class "Default")
      (node (ref "U27") (pin "F17") (pinfunction "PE15_F17") (pintype "passive"))
    )
    (net (code "183") (name "/eMMC.SDMMC2_D0") (class "Default")
      (node (ref "U27") (pin "B19") (pinfunction "PE13_B19") (pintype "passive"))
    )
    (net (code "184") (name "/eMMC.SDMMC2_D1") (class "Default")
      (node (ref "U27") (pin "E17") (pinfunction "PE11_E17") (pintype "passive"))
    )
    (net (code "185") (name "/eMMC.SDMMC2_D2") (class "Default")
      (node (ref "U27") (pin "C18") (pinfunction "PE8_C18") (pintype "passive"))
    )
    (net (code "186") (name "/eMMC.SDMMC2_D3") (class "Default")
      (node (ref "U27") (pin "C19") (pinfunction "PE12_C19") (pintype "passive"))
    )
    (net (code "187") (name "/eMMC.SDMMC2_D4") (class "Default")
      (node (ref "U27") (pin "A19") (pinfunction "PE10_A19") (pintype "passive"))
    )
    (net (code "188") (name "/eMMC.SDMMC2_D5") (class "Default")
      (node (ref "U27") (pin "D18") (pinfunction "PE9_D18") (pintype "passive"))
    )
    (net (code "189") (name "/eMMC.SDMMC2_D6") (class "Default")
      (node (ref "U27") (pin "E16") (pinfunction "PE6_E16") (pintype "passive"))
    )
    (net (code "190") (name "/eMMC.SDMMC2_D7") (class "Default")
      (node (ref "U27") (pin "D17") (pinfunction "PE7_D17") (pintype "passive"))
    )
    (net (code "192") (name "/mkB.AN") (class "Default")
      (node (ref "U27") (pin "V5") (pinfunction "ANA0_V5") (pintype "passive"))
    )
    (net (code "193") (name "/mkB.CS") (class "Default")
      (node (ref "U27") (pin "R6") (pinfunction "PZ6_R6") (pintype "passive"))
    )
    (net (code "194") (name "/mkB.INT") (class "Default")
      (node (ref "U27") (pin "N3") (pinfunction "PZ9_N3") (pintype "passive"))
    )
    (net (code "195") (name "/mkB.MISO") (class "Default")
      (node (ref "U27") (pin "N6") (pinfunction "PZ1_N6") (pintype "passive"))
    )
    (net (code "196") (name "/mkB.MOSI") (class "Default")
      (node (ref "U27") (pin "N5") (pinfunction "PZ0_N5") (pintype "passive"))
    )
    (net (code "197") (name "/mkB.PWM") (class "Default")
      (node (ref "U27") (pin "AB4") (pinfunction "PB15_AB4") (pintype "passive"))
    )
    (net (code "198") (name "/mkB.RST") (class "Default")
      (node (ref "U27") (pin "P5") (pinfunction "PZ5_P5") (pintype "passive"))
    )
    (net (code "199") (name "/mkB.RX") (class "Default")
      (node (ref "U27") (pin "P3") (pinfunction "PZ8_P3") (pintype "passive"))
    )
    (net (code "200") (name "/mkB.SCK") (class "Default")
      (node (ref "U27") (pin "P4") (pinfunction "PZ2_P4") (pintype "passive"))
    )
    (net (code "201") (name "/mkB.TX") (class "Default")
      (node (ref "U27") (pin "P2") (pinfunction "PZ7_P2") (pintype "passive"))
    )
    (net (code "218") (name "3V3") (class "Default")
      (node (ref "R224") (pin "2") (pinfunction "2_2") (pintype "passive"))
      (node (ref "R228") (pin "2") (pinfunction "2_2") (pintype "passive"))
    )
    (net (code "219") (name "GND") (class "Default")
      (node (ref "C336") (pin "1") (pinfunction "1_1") (pintype "passive"))
      (node (ref "C81") (pin "2") (pinfunction "2_2") (pintype "passive"))
      (node (ref "C86") (pin "2") (pinfunction "2_2") (pintype "passive"))
      (node (ref "C90") (pin "1") (pinfunction "1_1") (pintype "passive"))
      (node (ref "C91") (pin "1") (pinfunction "1_1") (pintype "passive"))
      (node (ref "C92") (pin "2") (pinfunction "2_2") (pintype "passive"))
      (node (ref "CN22") (pin "3") (pinfunction "3_3") (pintype "passive"))
      (node (ref "CN22") (pin "5") (pinfunction "5_5") (pintype "passive"))
      (node (ref "CN22") (pin "9") (pinfunction "9_9") (pintype "passive"))
      (node (ref "R205") (pin "2") (pinfunction "2_2") (pintype "passive"))
      (node (ref "R206") (pin "2") (pinfunction "2_2") (pintype "passive"))
      (node (ref "R72") (pin "2") (pinfunction "2_2") (pintype "passive"))
      (node (ref "R96") (pin "2") (pinfunction "2_2") (pintype "passive"))
      (node (ref "TP30") (pin "1") (pinfunction "1_1") (pintype "passive"))
      (node (ref "X2") (pin "2") (pinfunction "GND_2") (pintype "passive"))
    )
    (net (code "220") (name "Net-(U27C-PWR_LP)") (class "Default")
      (node (ref "TP12") (pin "1") (pinfunction "1_1") (pintype "passive"))
      (node (ref "U27") (pin "U4") (pinfunction "PWR_LP_U4") (pintype "passive"))
    )
    (net (code "221") (name "Net-(X1-X1)") (class "Default")
      (node (ref "C81") (pin "1") (pinfunction "1_1") (pintype "passive"))
      (node (ref "R64") (pin "2") (pinfunction "2_2") (pintype "passive"))
      (node (ref "X1") (pin "1") (pinfunction "X1_1") (pintype "passive"))
    )
    (net (code "222") (name "Net-(X2-EN)") (class "Default")
      (node (ref "C92") (pin "1") (pinfunction "1_1") (pintype "passive"))
      (node (ref "R74") (pin "1") (pinfunction "1_1") (pintype "passive"))
      (node (ref "R75") (pin "1") (pinfunction "1_1") (pintype "passive"))
      (node (ref "X2") (pin "1") (pinfunction "EN_1") (pintype "passive"))
    )
    (net (code "223") (name "Net-(X2-VDD)") (class "Default")
      (node (ref "C91") (pin "2") (pinfunction "2_2") (pintype "passive"))
      (node (ref "R70") (pin "2") (pinfunction "2_2") (pintype "passive"))
      (node (ref "X2") (pin "4") (pinfunction "VDD_4") (pintype "passive"))
    )
    (net (code "224") (name "VDDA1V8_AON") (class "Default")
      (node (ref "R70") (pin "1") (pinfunction "1_1") (pintype "passive"))
      (node (ref "U27") (pin "T7") (pinfunction "PDR_ON_T7") (pintype "passive"))
    )
    (net (code "225") (name "VDDIO") (class "Default")
      (node (ref "CN22") (pin "1") (pinfunction "1_1") (pintype "passive"))
      (node (ref "R107") (pin "2") (pinfunction "2_2") (pintype "passive"))
      (node (ref "R125") (pin "2") (pinfunction "2_2") (pintype "passive"))
      (node (ref "R245") (pin "2") (pinfunction "2_2") (pintype "passive"))
      (node (ref "R246") (pin "2") (pinfunction "2_2") (pintype "passive"))
      (node (ref "R260") (pin "2") (pinfunction "2_2") (pintype "passive"))
      (node (ref "R261") (pin "2") (pinfunction "2_2") (pintype "passive"))
      (node (ref "R27") (pin "2") (pinfunction "2_2") (pintype "passive"))
      (node (ref "R31") (pin "2") (pinfunction "2_2") (pintype "passive"))
      (node (ref "R32") (pin "2") (pinfunction "2_2") (pintype "passive"))
    )
    (net (code "226") (name "unconnected-(U27A-PB2-PadC10)") (class "Default")
      (node (ref "U27") (pin "C10") (pinfunction "PB2_C10") (pintype "passive+no_connect"))
    )
    (net (code "227") (name "unconnected-(U27A-PB3-PadE10)") (class "Default")
      (node (ref "U27") (pin "E10") (pinfunction "PB3_E10") (pintype "passive+no_connect"))
    )
    (net (code "228") (name "unconnected-(U27A-PB6-PadC12)") (class "Default")
      (node (ref "U27") (pin "C12") (pinfunction "PB6_C12") (pintype "passive+no_connect"))
    )
    (net (code "229") (name "unconnected-(U27A-PD1-PadE15)") (class "Default")
      (node (ref "U27") (pin "E15") (pinfunction "PD1_E15") (pintype "passive+no_connect"))
    )
    (net (code "230") (name "unconnected-(U27A-PD11-PadE13)") (class "Default")
      (node (ref "U27") (pin "E13") (pinfunction "PD11_E13") (pintype "passive+no_connect"))
    )
    (net (code "231") (name "unconnected-(U27B-PF12-PadK3)") (class "Default")
      (node (ref "U27") (pin "K3") (pinfunction "PF12_K3") (pintype "passive+no_connect"))
    )
    (net (code "232") (name "unconnected-(U27B-PG3-PadW4)") (class "Default")
      (node (ref "U27") (pin "W4") (pinfunction "PG3_W4") (pintype "passive+no_connect"))
    )
    (net (code "233") (name "unconnected-(U27B-PG4-PadAA4)") (class "Default")
      (node (ref "U27") (pin "AA4") (pinfunction "PG4_AA4") (pintype "passive+no_connect"))
    )
    (net (code "234") (name "unconnected-(U27C-ANA1-PadV6)") (class "Default")
      (node (ref "U27") (pin "V6") (pinfunction "ANA1_V6") (pintype "passive+no_connect"))
    )
    (net (code "235") (name "unconnected-(U27C-PI6-PadJ7)") (class "Default")
      (node (ref "U27") (pin "J7") (pinfunction "PI6_J7") (pintype "passive+no_connect"))
    )
    (net (code "236") (name "unconnected-(U27C-PI10-PadG16)") (class "Default")
      (node (ref "U27") (pin "G16") (pinfunction "PI10_G16") (pintype "passive+no_connect"))
    )
    (net (code "237") (name "unconnected-(U27C-PI15-PadE11)") (class "Default")
      (node (ref "U27") (pin "E11") (pinfunction "PI15_E11") (pintype "passive+no_connect"))
    )
    (net (code "238") (name "unconnected-(U27C-PJ10-PadM3)") (class "Default")
      (node (ref "U27") (pin "M3") (pinfunction "PJ10_M3") (pintype "passive+no_connect"))
    )
    (net (code "239") (name "unconnected-(U27C-PK2-PadF13)") (class "Default")
      (node (ref "U27") (pin "F13") (pinfunction "PK2_F13") (pintype "passive+no_connect"))
    )
    (net (code "240") (name "unconnected-(U27C-PK3-PadF15)") (class "Default")
      (node (ref "U27") (pin "F15") (pinfunction "PK3_F15") (pintype "passive+no_connect"))
    )
    (net (code "241") (name "unconnected-(U27C-PK4-PadF11)") (class "Default")
      (node (ref "U27") (pin "F11") (pinfunction "PK4_F11") (pintype "passive+no_connect"))
    )
    (net (code "242") (name "unconnected-(U27C-PK5-PadF14)") (class "Default")
      (node (ref "U27") (pin "F14") (pinfunction "PK5_F14") (pintype "passive+no_connect"))
    )
    (net (code "243") (name "unconnected-(U27C-PK6-PadG12)") (class "Default")
      (node (ref "U27") (pin "G12") (pinfunction "PK6_G12") (pintype "passive+no_connect"))
    )
    (net (code "244") (name "unconnected-(U27C-PK7-PadG14)") (class "Default")
      (node (ref "U27") (pin "G14") (pinfunction "PK7_G14") (pintype "passive+no_connect"))
    )
  )
)
